# Memory.net
KiCad netlist of a schematic drawn in Altium Designer
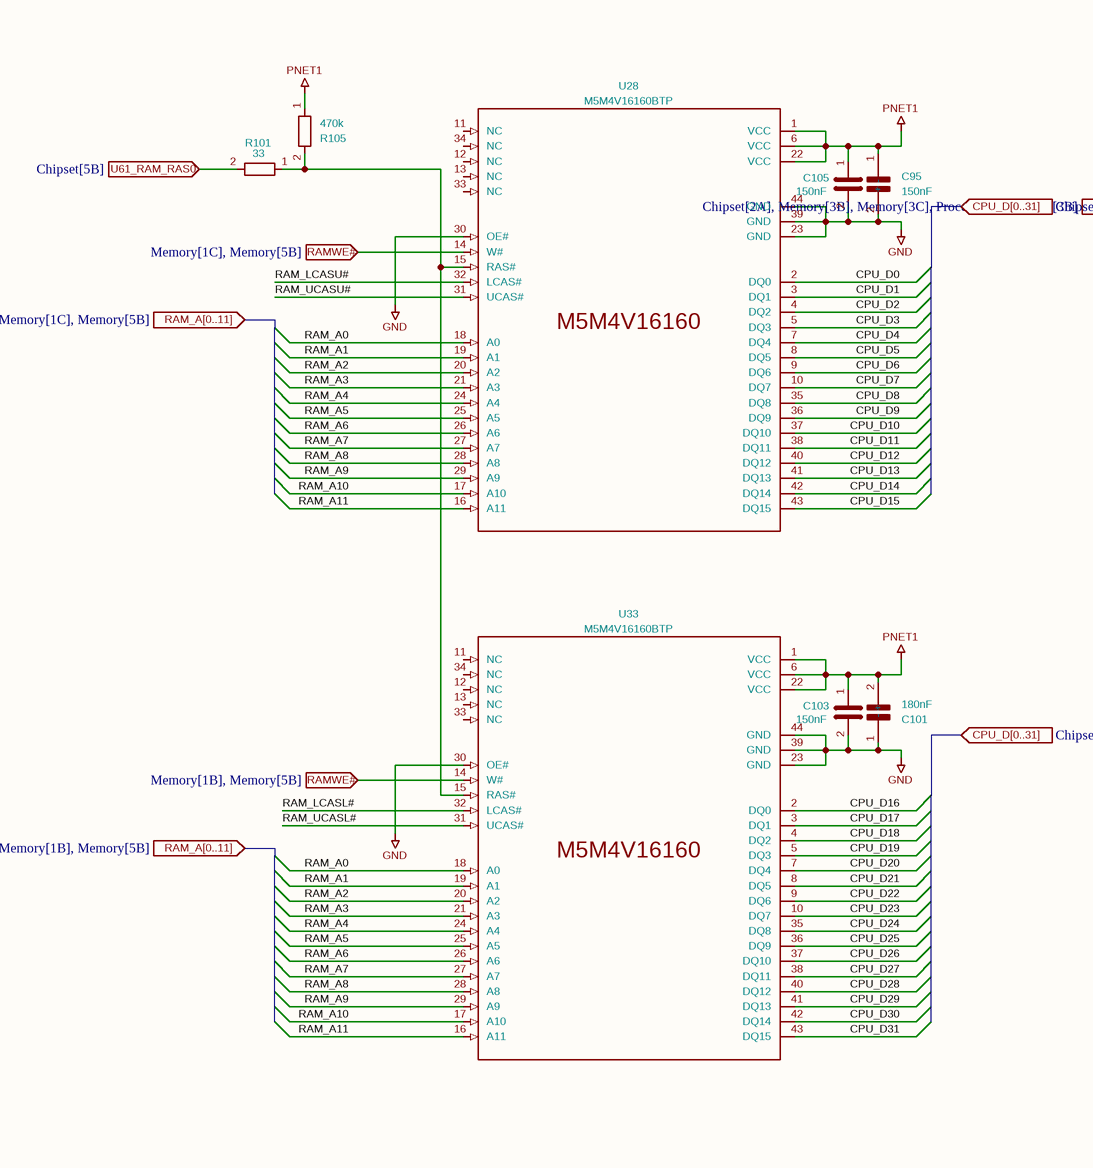
[diagram p0: Memory.SchDoc, left]
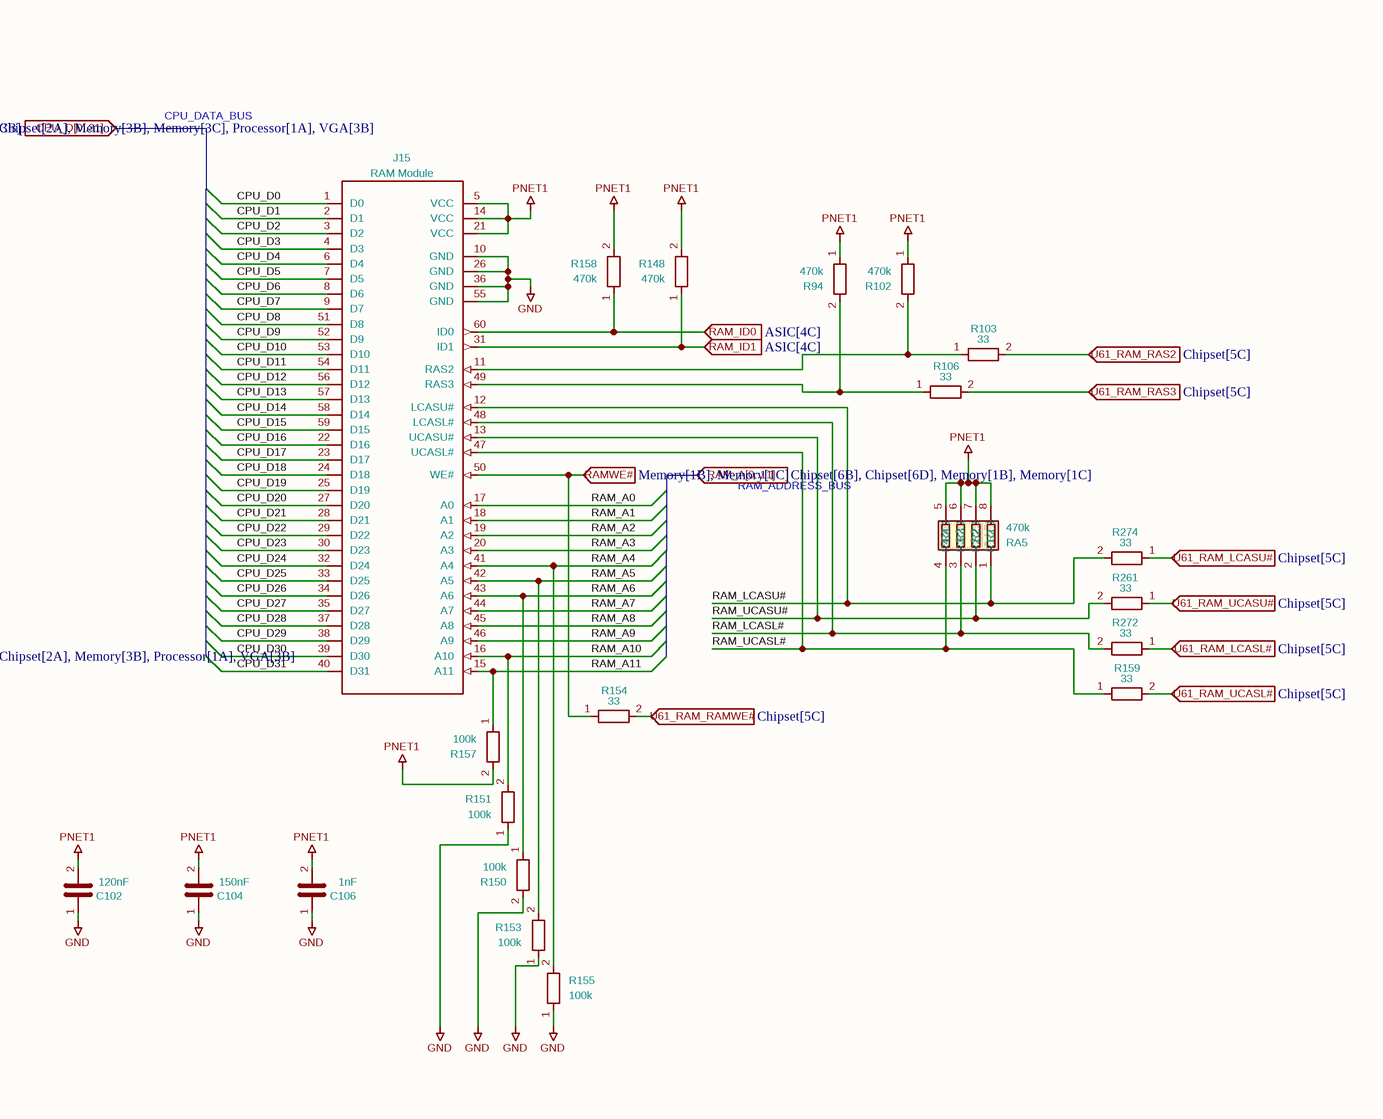
[diagram p1: Memory.SchDoc, right]

(export (version "E")
  (design (tool "Eeschema 10.0.6"))
  (components
    (comp (ref "C95") (value "150nF") (footprint "C_0402_1005Metric") (libsource (lib "") (part "C_1")))
    (comp (ref "C101")
      (value "180nF")
      (footprint "C_0402_1005Metric")
      (libsource (lib "PCM_Elektuur") (part "C"))
    )
    (comp (ref "C102") (value "120nF") (footprint "C_0402_1005Metric") (libsource (lib "Device") (part "C")))
    (comp (ref "C103") (value "150nF") (footprint "C_0402_1005Metric") (libsource (lib "Device") (part "C")))
    (comp (ref "C104") (value "150nF") (footprint "C_0402_1005Metric") (libsource (lib "Device") (part "C")))
    (comp (ref "C105") (value "150nF") (footprint "C_0402_1005Metric") (libsource (lib "Device") (part "C")))
    (comp (ref "C106") (value "1nF") (footprint "C_0402_1005Metric") (libsource (lib "Device") (part "C")))
    (comp (ref "J15")
      (value "RAM Module")
      (footprint "RAM Module")
      (libsource (lib "PC110") (part "RAM_MOD"))
    )
    (comp (ref "R94") (value "470k") (footprint "R_0402_1005Metric") (libsource (lib "") (part "R_1")))
    (comp (ref "R101") (value "33") (footprint "R_0402_1005Metric") (libsource (lib "") (part "R_1")))
    (comp (ref "R102") (value "470k") (footprint "R_0402_1005Metric") (libsource (lib "") (part "R_1")))
    (comp (ref "R103") (value "33") (footprint "R_0402_1005Metric") (libsource (lib "Device") (part "R")))
    (comp (ref "R105") (value "470k") (footprint "R_0402_1005Metric") (libsource (lib "") (part "R_2")))
    (comp (ref "R106") (value "33") (footprint "R_0402_1005Metric") (libsource (lib "Device") (part "R")))
    (comp (ref "R148") (value "470k") (footprint "R_0402_1005Metric") (libsource (lib "Device") (part "R")))
    (comp (ref "R150") (value "100k") (footprint "R_0402_1005Metric") (libsource (lib "") (part "R_1")))
    (comp (ref "R151") (value "100k") (footprint "R_0402_1005Metric") (libsource (lib "Device") (part "R")))
    (comp (ref "R153") (value "100k") (footprint "R_0402_1005Metric") (libsource (lib "Device") (part "R")))
    (comp (ref "R154") (value "33") (footprint "R_0402_1005Metric") (libsource (lib "Device") (part "R")))
    (comp (ref "R155") (value "100k") (footprint "R_0402_1005Metric") (libsource (lib "") (part "R_3")))
    (comp (ref "R157") (value "100k") (footprint "R_0402_1005Metric") (libsource (lib "") (part "R_1")))
    (comp (ref "R158") (value "470k") (footprint "R_0402_1005Metric") (libsource (lib "Device") (part "R")))
    (comp (ref "R159") (value "33") (footprint "R_0402_1005Metric") (libsource (lib "Device") (part "R")))
    (comp (ref "R261") (value "33") (footprint "R_0402_1005Metric") (libsource (lib "") (part "R_1")))
    (comp (ref "R272") (value "33") (footprint "R_0402_1005Metric") (libsource (lib "") (part "R_1")))
    (comp (ref "R274") (value "33") (footprint "R_0402_1005Metric") (libsource (lib "") (part "R_1")))
    (comp (ref "RA5") (value "470k") (footprint "R-array") (libsource (lib "Device") (part "R_Pack04")))
    (comp (ref "U28")
      (value "M5M4V16160BTP")
      (footprint "RAMchip")
      (libsource (lib "PC110") (part "M5M4V16160"))
    )
    (comp (ref "U33")
      (value "M5M4V16160BTP")
      (footprint "RAMchip")
      (libsource (lib "PC110") (part "M5M4V16160"))
    )
  )
  (nets
    (net (code "1") (name "/CPU_D0") (class "Default")
      (node (ref "J15") (pin "1") (pinfunction "D0_1") (pintype "bidirectional"))
      (node (ref "U28") (pin "2") (pinfunction "DQ0_2") (pintype "bidirectional"))
    )
    (net (code "2") (name "/CPU_D1") (class "Default")
      (node (ref "J15") (pin "2") (pinfunction "D1_2") (pintype "bidirectional"))
      (node (ref "U28") (pin "3") (pinfunction "DQ1_3") (pintype "bidirectional"))
    )
    (net (code "3") (name "/CPU_D2") (class "Default")
      (node (ref "J15") (pin "3") (pinfunction "D2_3") (pintype "bidirectional"))
      (node (ref "U28") (pin "4") (pinfunction "DQ2_4") (pintype "bidirectional"))
    )
    (net (code "4") (name "/CPU_D3") (class "Default")
      (node (ref "J15") (pin "4") (pinfunction "D3_4") (pintype "bidirectional"))
      (node (ref "U28") (pin "5") (pinfunction "DQ3_5") (pintype "bidirectional"))
    )
    (net (code "5") (name "/CPU_D4") (class "Default")
      (node (ref "J15") (pin "6") (pinfunction "D4_6") (pintype "bidirectional"))
      (node (ref "U28") (pin "7") (pinfunction "DQ4_7") (pintype "bidirectional"))
    )
    (net (code "6") (name "/CPU_D5") (class "Default")
      (node (ref "J15") (pin "7") (pinfunction "D5_7") (pintype "bidirectional"))
      (node (ref "U28") (pin "8") (pinfunction "DQ5_8") (pintype "bidirectional"))
    )
    (net (code "7") (name "/CPU_D6") (class "Default")
      (node (ref "J15") (pin "8") (pinfunction "D6_8") (pintype "bidirectional"))
      (node (ref "U28") (pin "9") (pinfunction "DQ6_9") (pintype "bidirectional"))
    )
    (net (code "8") (name "/CPU_D7") (class "Default")
      (node (ref "J15") (pin "9") (pinfunction "D7_9") (pintype "bidirectional"))
      (node (ref "U28") (pin "10") (pinfunction "DQ7_10") (pintype "bidirectional"))
    )
    (net (code "9") (name "/CPU_D8") (class "Default")
      (node (ref "J15") (pin "51") (pinfunction "D8_51") (pintype "bidirectional"))
      (node (ref "U28") (pin "35") (pinfunction "DQ8_35") (pintype "bidirectional"))
    )
    (net (code "10") (name "/CPU_D9") (class "Default")
      (node (ref "J15") (pin "52") (pinfunction "D9_52") (pintype "bidirectional"))
      (node (ref "U28") (pin "36") (pinfunction "DQ9_36") (pintype "bidirectional"))
    )
    (net (code "11") (name "/CPU_D10") (class "Default")
      (node (ref "J15") (pin "53") (pinfunction "D10_53") (pintype "bidirectional"))
      (node (ref "U28") (pin "37") (pinfunction "DQ10_37") (pintype "bidirectional"))
    )
    (net (code "12") (name "/CPU_D11") (class "Default")
      (node (ref "J15") (pin "54") (pinfunction "D11_54") (pintype "bidirectional"))
      (node (ref "U28") (pin "38") (pinfunction "DQ11_38") (pintype "bidirectional"))
    )
    (net (code "13") (name "/CPU_D12") (class "Default")
      (node (ref "J15") (pin "56") (pinfunction "D12_56") (pintype "bidirectional"))
      (node (ref "U28") (pin "40") (pinfunction "DQ12_40") (pintype "bidirectional"))
    )
    (net (code "14") (name "/CPU_D13") (class "Default")
      (node (ref "J15") (pin "57") (pinfunction "D13_57") (pintype "bidirectional"))
      (node (ref "U28") (pin "41") (pinfunction "DQ13_41") (pintype "bidirectional"))
    )
    (net (code "15") (name "/CPU_D14") (class "Default")
      (node (ref "J15") (pin "58") (pinfunction "D14_58") (pintype "bidirectional"))
      (node (ref "U28") (pin "42") (pinfunction "DQ14_42") (pintype "bidirectional"))
    )
    (net (code "16") (name "/CPU_D15") (class "Default")
      (node (ref "J15") (pin "59") (pinfunction "D15_59") (pintype "bidirectional"))
      (node (ref "U28") (pin "43") (pinfunction "DQ15_43") (pintype "bidirectional"))
    )
    (net (code "17") (name "/CPU_D16") (class "Default")
      (node (ref "J15") (pin "22") (pinfunction "D16_22") (pintype "bidirectional"))
      (node (ref "U33") (pin "2") (pinfunction "DQ0_2") (pintype "bidirectional"))
    )
    (net (code "18") (name "/CPU_D17") (class "Default")
      (node (ref "J15") (pin "23") (pinfunction "D17_23") (pintype "bidirectional"))
      (node (ref "U33") (pin "3") (pinfunction "DQ1_3") (pintype "bidirectional"))
    )
    (net (code "19") (name "/CPU_D18") (class "Default")
      (node (ref "J15") (pin "24") (pinfunction "D18_24") (pintype "bidirectional"))
      (node (ref "U33") (pin "4") (pinfunction "DQ2_4") (pintype "bidirectional"))
    )
    (net (code "20") (name "/CPU_D19") (class "Default")
      (node (ref "J15") (pin "25") (pinfunction "D19_25") (pintype "bidirectional"))
      (node (ref "U33") (pin "5") (pinfunction "DQ3_5") (pintype "bidirectional"))
    )
    (net (code "21") (name "/CPU_D20") (class "Default")
      (node (ref "J15") (pin "27") (pinfunction "D20_27") (pintype "bidirectional"))
      (node (ref "U33") (pin "7") (pinfunction "DQ4_7") (pintype "bidirectional"))
    )
    (net (code "22") (name "/CPU_D21") (class "Default")
      (node (ref "J15") (pin "28") (pinfunction "D21_28") (pintype "bidirectional"))
      (node (ref "U33") (pin "8") (pinfunction "DQ5_8") (pintype "bidirectional"))
    )
    (net (code "23") (name "/CPU_D22") (class "Default")
      (node (ref "J15") (pin "29") (pinfunction "D22_29") (pintype "bidirectional"))
      (node (ref "U33") (pin "9") (pinfunction "DQ6_9") (pintype "bidirectional"))
    )
    (net (code "24") (name "/CPU_D23") (class "Default")
      (node (ref "J15") (pin "30") (pinfunction "D23_30") (pintype "bidirectional"))
      (node (ref "U33") (pin "10") (pinfunction "DQ7_10") (pintype "bidirectional"))
    )
    (net (code "25") (name "/CPU_D24") (class "Default")
      (node (ref "J15") (pin "32") (pinfunction "D24_32") (pintype "bidirectional"))
      (node (ref "U33") (pin "35") (pinfunction "DQ8_35") (pintype "bidirectional"))
    )
    (net (code "26") (name "/CPU_D25") (class "Default")
      (node (ref "J15") (pin "33") (pinfunction "D25_33") (pintype "bidirectional"))
      (node (ref "U33") (pin "36") (pinfunction "DQ9_36") (pintype "bidirectional"))
    )
    (net (code "27") (name "/CPU_D26") (class "Default")
      (node (ref "J15") (pin "34") (pinfunction "D26_34") (pintype "bidirectional"))
      (node (ref "U33") (pin "37") (pinfunction "DQ10_37") (pintype "bidirectional"))
    )
    (net (code "28") (name "/CPU_D27") (class "Default")
      (node (ref "J15") (pin "35") (pinfunction "D27_35") (pintype "bidirectional"))
      (node (ref "U33") (pin "38") (pinfunction "DQ11_38") (pintype "bidirectional"))
    )
    (net (code "29") (name "/CPU_D28") (class "Default")
      (node (ref "J15") (pin "37") (pinfunction "D28_37") (pintype "bidirectional"))
      (node (ref "U33") (pin "40") (pinfunction "DQ12_40") (pintype "bidirectional"))
    )
    (net (code "30") (name "/CPU_D29") (class "Default")
      (node (ref "J15") (pin "38") (pinfunction "D29_38") (pintype "bidirectional"))
      (node (ref "U33") (pin "41") (pinfunction "DQ13_41") (pintype "bidirectional"))
    )
    (net (code "31") (name "/CPU_D30") (class "Default")
      (node (ref "J15") (pin "39") (pinfunction "D30_39") (pintype "bidirectional"))
      (node (ref "U33") (pin "42") (pinfunction "DQ14_42") (pintype "bidirectional"))
    )
    (net (code "32") (name "/CPU_D31") (class "Default")
      (node (ref "J15") (pin "40") (pinfunction "D31_40") (pintype "bidirectional"))
      (node (ref "U33") (pin "43") (pinfunction "DQ15_43") (pintype "bidirectional"))
    )
    (net (code "34") (name "/RAMWE#") (class "Default")
      (node (ref "J15") (pin "50") (pinfunction "WE#_50") (pintype "input"))
      (node (ref "R154") (pin "1") (pinfunction "1_1") (pintype "passive"))
      (node (ref "U28") (pin "14") (pinfunction "W#_14") (pintype "input"))
      (node (ref "U33") (pin "14") (pinfunction "W#_14") (pintype "input"))
    )
    (net (code "35") (name "/RAM_A0") (class "Default")
      (node (ref "J15") (pin "17") (pinfunction "A0_17") (pintype "input"))
      (node (ref "U28") (pin "18") (pinfunction "A0_18") (pintype "input"))
      (node (ref "U33") (pin "18") (pinfunction "A0_18") (pintype "input"))
    )
    (net (code "36") (name "/RAM_A1") (class "Default")
      (node (ref "J15") (pin "18") (pinfunction "A1_18") (pintype "input"))
      (node (ref "U28") (pin "19") (pinfunction "A1_19") (pintype "input"))
      (node (ref "U33") (pin "19") (pinfunction "A1_19") (pintype "input"))
    )
    (net (code "37") (name "/RAM_A2") (class "Default")
      (node (ref "J15") (pin "19") (pinfunction "A2_19") (pintype "input"))
      (node (ref "U28") (pin "20") (pinfunction "A2_20") (pintype "input"))
      (node (ref "U33") (pin "20") (pinfunction "A2_20") (pintype "input"))
    )
    (net (code "38") (name "/RAM_A3") (class "Default")
      (node (ref "J15") (pin "20") (pinfunction "A3_20") (pintype "input"))
      (node (ref "U28") (pin "21") (pinfunction "A3_21") (pintype "input"))
      (node (ref "U33") (pin "21") (pinfunction "A3_21") (pintype "input"))
    )
    (net (code "39") (name "/RAM_A4") (class "Default")
      (node (ref "J15") (pin "41") (pinfunction "A4_41") (pintype "input"))
      (node (ref "R155") (pin "2") (pinfunction "2_2") (pintype "passive"))
      (node (ref "U28") (pin "24") (pinfunction "A4_24") (pintype "input"))
      (node (ref "U33") (pin "24") (pinfunction "A4_24") (pintype "input"))
    )
    (net (code "40") (name "/RAM_A5") (class "Default")
      (node (ref "J15") (pin "42") (pinfunction "A5_42") (pintype "input"))
      (node (ref "R153") (pin "2") (pinfunction "2_2") (pintype "passive"))
      (node (ref "U28") (pin "25") (pinfunction "A5_25") (pintype "input"))
      (node (ref "U33") (pin "25") (pinfunction "A5_25") (pintype "input"))
    )
    (net (code "41") (name "/RAM_A6") (class "Default")
      (node (ref "J15") (pin "43") (pinfunction "A6_43") (pintype "input"))
      (node (ref "R150") (pin "1") (pinfunction "1_1") (pintype "passive"))
      (node (ref "U28") (pin "26") (pinfunction "A6_26") (pintype "input"))
      (node (ref "U33") (pin "26") (pinfunction "A6_26") (pintype "input"))
    )
    (net (code "42") (name "/RAM_A7") (class "Default")
      (node (ref "J15") (pin "44") (pinfunction "A7_44") (pintype "input"))
      (node (ref "U28") (pin "27") (pinfunction "A7_27") (pintype "input"))
      (node (ref "U33") (pin "27") (pinfunction "A7_27") (pintype "input"))
    )
    (net (code "43") (name "/RAM_A8") (class "Default")
      (node (ref "J15") (pin "45") (pinfunction "A8_45") (pintype "input"))
      (node (ref "U28") (pin "28") (pinfunction "A8_28") (pintype "input"))
      (node (ref "U33") (pin "28") (pinfunction "A8_28") (pintype "input"))
    )
    (net (code "44") (name "/RAM_A9") (class "Default")
      (node (ref "J15") (pin "46") (pinfunction "A9_46") (pintype "input"))
      (node (ref "U28") (pin "29") (pinfunction "A9_29") (pintype "input"))
      (node (ref "U33") (pin "29") (pinfunction "A9_29") (pintype "input"))
    )
    (net (code "45") (name "/RAM_A10") (class "Default")
      (node (ref "J15") (pin "16") (pinfunction "A10_16") (pintype "input"))
      (node (ref "R151") (pin "2") (pinfunction "2_2") (pintype "passive"))
      (node (ref "U28") (pin "17") (pinfunction "A10_17") (pintype "input"))
      (node (ref "U33") (pin "17") (pinfunction "A10_17") (pintype "input"))
    )
    (net (code "46") (name "/RAM_A11") (class "Default")
      (node (ref "J15") (pin "15") (pinfunction "A11_15") (pintype "input"))
      (node (ref "R157") (pin "1") (pinfunction "1_1") (pintype "passive"))
      (node (ref "U28") (pin "16") (pinfunction "A11_16") (pintype "input"))
      (node (ref "U33") (pin "16") (pinfunction "A11_16") (pintype "input"))
    )
    (net (code "48") (name "/RAM_ID0") (class "Default")
      (node (ref "J15") (pin "60") (pinfunction "ID0_60") (pintype "output"))
      (node (ref "R158") (pin "1") (pinfunction "1_1") (pintype "passive"))
    )
    (net (code "49") (name "/RAM_ID1") (class "Default")
      (node (ref "J15") (pin "31") (pinfunction "ID1_31") (pintype "output"))
      (node (ref "R148") (pin "1") (pinfunction "1_1") (pintype "passive"))
    )
    (net (code "50") (name "/RAM_LCASL#") (class "Default")
      (node (ref "J15") (pin "48") (pinfunction "LCASL#_48") (pintype "input"))
      (node (ref "R272") (pin "2") (pinfunction "2_2") (pintype "passive"))
      (node (ref "RA5") (pin "3") (pinfunction "R3.1_3") (pintype "passive"))
      (node (ref "U33") (pin "32") (pinfunction "LCAS#_32") (pintype "input"))
    )
    (net (code "51") (name "/RAM_LCASU#") (class "Default")
      (node (ref "J15") (pin "12") (pinfunction "LCASU#_12") (pintype "input"))
      (node (ref "R274") (pin "2") (pinfunction "2_2") (pintype "passive"))
      (node (ref "RA5") (pin "1") (pinfunction "R1.1_1") (pintype "passive"))
      (node (ref "U28") (pin "32") (pinfunction "LCAS#_32") (pintype "input"))
    )
    (net (code "52") (name "/RAM_UCASL#") (class "Default")
      (node (ref "J15") (pin "47") (pinfunction "UCASL#_47") (pintype "input"))
      (node (ref "R159") (pin "1") (pinfunction "1_1") (pintype "passive"))
      (node (ref "RA5") (pin "4") (pinfunction "R4.1_4") (pintype "passive"))
      (node (ref "U33") (pin "31") (pinfunction "UCAS#_31") (pintype "input"))
    )
    (net (code "53") (name "/RAM_UCASU#") (class "Default")
      (node (ref "J15") (pin "13") (pinfunction "UCASU#_13") (pintype "input"))
      (node (ref "R261") (pin "2") (pinfunction "2_2") (pintype "passive"))
      (node (ref "RA5") (pin "2") (pinfunction "R2.1_2") (pintype "passive"))
      (node (ref "U28") (pin "31") (pinfunction "UCAS#_31") (pintype "input"))
    )
    (net (code "54") (name "/U61_RAM_LCASL#") (class "Default")
      (node (ref "R272") (pin "1") (pinfunction "1_1") (pintype "passive"))
    )
    (net (code "55") (name "/U61_RAM_LCASU#") (class "Default")
      (node (ref "R274") (pin "1") (pinfunction "1_1") (pintype "passive"))
    )
    (net (code "56") (name "/U61_RAM_RAMWE#") (class "Default")
      (node (ref "R154") (pin "2") (pinfunction "2_2") (pintype "passive"))
    )
    (net (code "57") (name "/U61_RAM_RAS0") (class "Default")
      (node (ref "R101") (pin "2") (pinfunction "2_2") (pintype "passive"))
    )
    (net (code "58") (name "/U61_RAM_RAS2") (class "Default")
      (node (ref "R103") (pin "2") (pinfunction "2_2") (pintype "passive"))
    )
    (net (code "59") (name "/U61_RAM_RAS3") (class "Default")
      (node (ref "R106") (pin "2") (pinfunction "2_2") (pintype "passive"))
    )
    (net (code "60") (name "/U61_RAM_UCASL#") (class "Default")
      (node (ref "R159") (pin "2") (pinfunction "2_2") (pintype "passive"))
    )
    (net (code "61") (name "/U61_RAM_UCASU#") (class "Default")
      (node (ref "R261") (pin "1") (pinfunction "1_1") (pintype "passive"))
    )
    (net (code "62") (name "GND") (class "Default")
      (node (ref "C101") (pin "1") (pinfunction "+_1") (pintype "passive"))
      (node (ref "C102") (pin "1") (pinfunction "1_1") (pintype "passive"))
      (node (ref "C103") (pin "2") (pinfunction "2_2") (pintype "passive"))
      (node (ref "C104") (pin "1") (pinfunction "1_1") (pintype "passive"))
      (node (ref "C105") (pin "2") (pinfunction "2_2") (pintype "passive"))
      (node (ref "C106") (pin "1") (pinfunction "1_1") (pintype "passive"))
      (node (ref "C95") (pin "2") (pinfunction "-_2") (pintype "passive"))
      (node (ref "J15") (pin "10") (pinfunction "GND_10") (pintype "power_in"))
      (node (ref "J15") (pin "26") (pinfunction "GND_26") (pintype "power_in"))
      (node (ref "J15") (pin "36") (pinfunction "GND_36") (pintype "power_in"))
      (node (ref "J15") (pin "55") (pinfunction "GND_55") (pintype "power_in"))
      (node (ref "R150") (pin "2") (pinfunction "2_2") (pintype "passive"))
      (node (ref "R151") (pin "1") (pinfunction "1_1") (pintype "passive"))
      (node (ref "R153") (pin "1") (pinfunction "1_1") (pintype "passive"))
      (node (ref "R155") (pin "1") (pinfunction "1_1") (pintype "passive"))
      (node (ref "U28") (pin "23") (pinfunction "GND_23") (pintype "power_in"))
      (node (ref "U28") (pin "30") (pinfunction "OE#_30") (pintype "input"))
      (node (ref "U28") (pin "39") (pinfunction "GND_39") (pintype "power_in"))
      (node (ref "U28") (pin "44") (pinfunction "GND_44") (pintype "power_in"))
      (node (ref "U33") (pin "23") (pinfunction "GND_23") (pintype "power_in"))
      (node (ref "U33") (pin "30") (pinfunction "OE#_30") (pintype "input"))
      (node (ref "U33") (pin "39") (pinfunction "GND_39") (pintype "power_in"))
      (node (ref "U33") (pin "44") (pinfunction "GND_44") (pintype "power_in"))
    )
    (net (code "63") (name "Net-(J15-RAS2)") (class "Default")
      (node (ref "J15") (pin "11") (pinfunction "RAS2_11") (pintype "input"))
      (node (ref "R102") (pin "2") (pinfunction "2_2") (pintype "passive"))
      (node (ref "R103") (pin "1") (pinfunction "1_1") (pintype "passive"))
    )
    (net (code "64") (name "Net-(J15-RAS3)") (class "Default")
      (node (ref "J15") (pin "49") (pinfunction "RAS3_49") (pintype "input"))
      (node (ref "R106") (pin "1") (pinfunction "1_1") (pintype "passive"))
      (node (ref "R94") (pin "2") (pinfunction "2_2") (pintype "passive"))
    )
    (net (code "65") (name "Net-(U28-RAS#)") (class "Default")
      (node (ref "R101") (pin "1") (pinfunction "1_1") (pintype "passive"))
      (node (ref "R105") (pin "2") (pinfunction "2_2") (pintype "passive"))
      (node (ref "U28") (pin "15") (pinfunction "RAS#_15") (pintype "input"))
      (node (ref "U33") (pin "15") (pinfunction "RAS#_15") (pintype "input"))
    )
    (net (code "66") (name "PNET1") (class "Default")
      (node (ref "C101") (pin "2") (pinfunction "-_2") (pintype "passive"))
      (node (ref "C102") (pin "2") (pinfunction "2_2") (pintype "passive"))
      (node (ref "C103") (pin "1") (pinfunction "1_1") (pintype "passive"))
      (node (ref "C104") (pin "2") (pinfunction "2_2") (pintype "passive"))
      (node (ref "C105") (pin "1") (pinfunction "1_1") (pintype "passive"))
      (node (ref "C106") (pin "2") (pinfunction "2_2") (pintype "passive"))
      (node (ref "C95") (pin "1") (pinfunction "+_1") (pintype "passive"))
      (node (ref "J15") (pin "14") (pinfunction "VCC_14") (pintype "power_in"))
      (node (ref "J15") (pin "21") (pinfunction "VCC_21") (pintype "power_in"))
      (node (ref "J15") (pin "5") (pinfunction "VCC_5") (pintype "power_in"))
      (node (ref "R102") (pin "1") (pinfunction "1_1") (pintype "passive"))
      (node (ref "R105") (pin "1") (pinfunction "1_1") (pintype "passive"))
      (node (ref "R148") (pin "2") (pinfunction "2_2") (pintype "passive"))
      (node (ref "R157") (pin "2") (pinfunction "2_2") (pintype "passive"))
      (node (ref "R158") (pin "2") (pinfunction "2_2") (pintype "passive"))
      (node (ref "R94") (pin "1") (pinfunction "1_1") (pintype "passive"))
      (node (ref "RA5") (pin "5") (pinfunction "R4.2_5") (pintype "passive"))
      (node (ref "RA5") (pin "6") (pinfunction "R3.2_6") (pintype "passive"))
      (node (ref "RA5") (pin "7") (pinfunction "R2.2_7") (pintype "passive"))
      (node (ref "RA5") (pin "8") (pinfunction "R1.2_8") (pintype "passive"))
      (node (ref "U28") (pin "1") (pinfunction "VCC_1") (pintype "power_in"))
      (node (ref "U28") (pin "22") (pinfunction "VCC_22") (pintype "power_in"))
      (node (ref "U28") (pin "6") (pinfunction "VCC_6") (pintype "power_in"))
      (node (ref "U33") (pin "1") (pinfunction "VCC_1") (pintype "power_in"))
      (node (ref "U33") (pin "22") (pinfunction "VCC_22") (pintype "power_in"))
      (node (ref "U33") (pin "6") (pinfunction "VCC_6") (pintype "power_in"))
    )
    (net (code "67") (name "unconnected-(U28-NC-Pad11)") (class "Default")
      (node (ref "U28") (pin "11") (pinfunction "NC_11") (pintype "input"))
    )
    (net (code "68") (name "unconnected-(U28-NC-Pad12)") (class "Default")
      (node (ref "U28") (pin "12") (pinfunction "NC_12") (pintype "input"))
    )
    (net (code "69") (name "unconnected-(U28-NC-Pad13)") (class "Default")
      (node (ref "U28") (pin "13") (pinfunction "NC_13") (pintype "input"))
    )
    (net (code "70") (name "unconnected-(U28-NC-Pad33)") (class "Default")
      (node (ref "U28") (pin "33") (pinfunction "NC_33") (pintype "input"))
    )
    (net (code "71") (name "unconnected-(U28-NC-Pad34)") (class "Default")
      (node (ref "U28") (pin "34") (pinfunction "NC_34") (pintype "input"))
    )
    (net (code "72") (name "unconnected-(U33-NC-Pad11)") (class "Default")
      (node (ref "U33") (pin "11") (pinfunction "NC_11") (pintype "input"))
    )
    (net (code "73") (name "unconnected-(U33-NC-Pad12)") (class "Default")
      (node (ref "U33") (pin "12") (pinfunction "NC_12") (pintype "input"))
    )
    (net (code "74") (name "unconnected-(U33-NC-Pad13)") (class "Default")
      (node (ref "U33") (pin "13") (pinfunction "NC_13") (pintype "input"))
    )
    (net (code "75") (name "unconnected-(U33-NC-Pad33)") (class "Default")
      (node (ref "U33") (pin "33") (pinfunction "NC_33") (pintype "input"))
    )
    (net (code "76") (name "unconnected-(U33-NC-Pad34)") (class "Default")
      (node (ref "U33") (pin "34") (pinfunction "NC_34") (pintype "input"))
    )
  )
)
